# servo_power.net
KiCad netlist of a schematic drawn in EAGLE
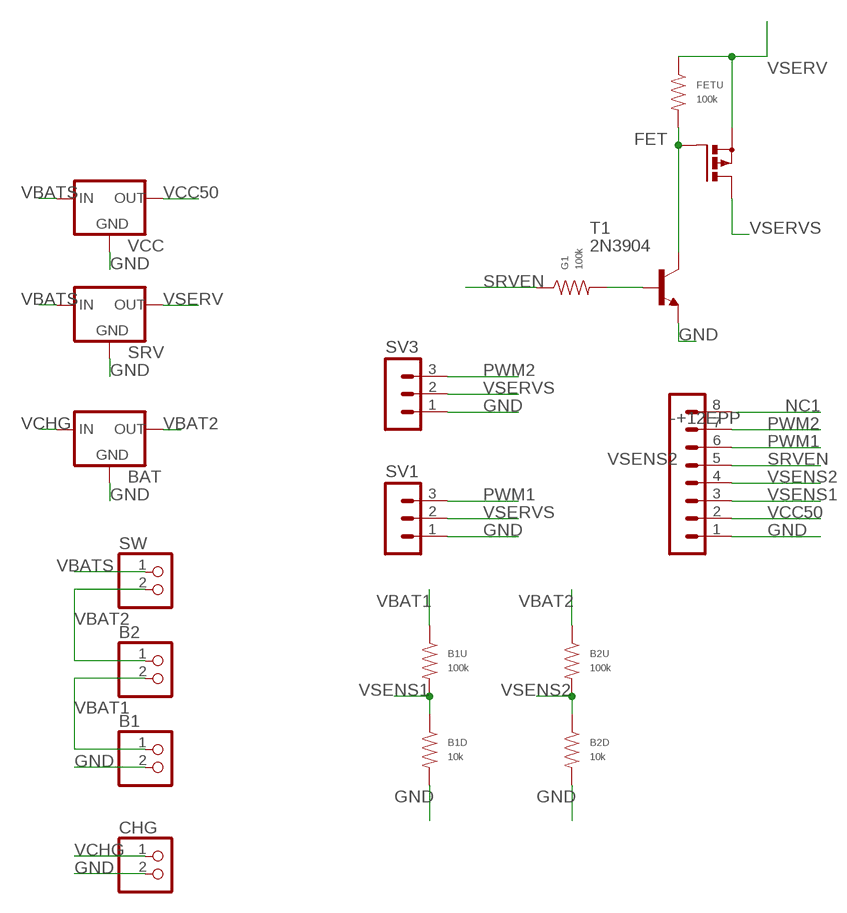
[diagram p0: schematic, sheet 1]

(export (version "E")
  (design (tool "Eeschema 10.0.6"))
  (components
    (comp (ref "-+12EPP")
      (value "MA08-1")
      (footprint "eagle-import:MA08-1")
      (libsource (lib "eagle-import") (part "MA08-1"))
    )
    (comp (ref "B1")
      (value "PINHD-1X2")
      (footprint "eagle-import:1X02")
      (libsource (lib "eagle-import") (part "PINHD-1X2"))
    )
    (comp (ref "B1D")
      (value "10k")
      (footprint "eagle-import:R1206")
      (libsource (lib "eagle-import") (part "RESISTOR_1206"))
    )
    (comp (ref "B1U")
      (value "100k")
      (footprint "eagle-import:R1206")
      (libsource (lib "eagle-import") (part "RESISTOR_1206"))
    )
    (comp (ref "B2")
      (value "PINHD-1X2")
      (footprint "eagle-import:1X02")
      (libsource (lib "eagle-import") (part "PINHD-1X2"))
    )
    (comp (ref "B2D")
      (value "10k")
      (footprint "eagle-import:R1206")
      (libsource (lib "eagle-import") (part "RESISTOR_1206"))
    )
    (comp (ref "B2U")
      (value "100k")
      (footprint "eagle-import:R1206")
      (libsource (lib "eagle-import") (part "RESISTOR_1206"))
    )
    (comp (ref "BAT")
      (value "78XXS")
      (footprint "eagle-import:78XXS")
      (libsource (lib "eagle-import") (part "78XXS"))
    )
    (comp (ref "CHG")
      (value "PINHD-1X2")
      (footprint "eagle-import:1X02")
      (libsource (lib "eagle-import") (part "PINHD-1X2"))
    )
    (comp (ref "FET")
      (value "PMOSFET_PTO220BV")
      (footprint "eagle-import:TO220BV")
      (libsource (lib "eagle-import") (part "PMOSFET_PTO220BV"))
    )
    (comp (ref "FETU")
      (value "100k")
      (footprint "eagle-import:R1206")
      (libsource (lib "eagle-import") (part "RESISTOR_1206"))
    )
    (comp (ref "G1")
      (value "100k")
      (footprint "eagle-import:R1206")
      (libsource (lib "eagle-import") (part "RESISTOR_1206"))
    )
    (comp (ref "SRV")
      (value "78XXS")
      (footprint "eagle-import:78XXS")
      (libsource (lib "eagle-import") (part "78XXS"))
    )
    (comp (ref "SV1")
      (value "MA03-1")
      (footprint "eagle-import:MA03-1")
      (libsource (lib "eagle-import") (part "MA03-1"))
    )
    (comp (ref "SV3")
      (value "MA03-1")
      (footprint "eagle-import:MA03-1")
      (libsource (lib "eagle-import") (part "MA03-1"))
    )
    (comp (ref "SW")
      (value "PINHD-1X2")
      (footprint "eagle-import:1X02")
      (libsource (lib "eagle-import") (part "PINHD-1X2"))
    )
    (comp (ref "T1")
      (value "2N3904")
      (footprint "eagle-import:TO92")
      (libsource (lib "eagle-import") (part "2N3904"))
    )
    (comp (ref "VCC")
      (value "78XXS")
      (footprint "eagle-import:78XXS")
      (libsource (lib "eagle-import") (part "78XXS"))
    )
  )
  (nets
    (net (code "1") (name "GND") (class "Default")
      (node (ref "-+12EPP") (pin "1") (pinfunction "1_1") (pintype "passive"))
      (node (ref "B1") (pin "2") (pinfunction "2_2") (pintype "passive"))
      (node (ref "B1D") (pin "P$2") (pinfunction "P$2_P$2") (pintype "passive"))
      (node (ref "B2D") (pin "P$2") (pinfunction "P$2_P$2") (pintype "passive"))
      (node (ref "BAT") (pin "GND") (pinfunction "GND_GND") (pintype "input"))
      (node (ref "CHG") (pin "2") (pinfunction "2_2") (pintype "passive"))
      (node (ref "SRV") (pin "GND") (pinfunction "GND_GND") (pintype "input"))
      (node (ref "SV1") (pin "1") (pinfunction "1_1") (pintype "passive"))
      (node (ref "SV3") (pin "1") (pinfunction "1_1") (pintype "passive"))
      (node (ref "T1") (pin "3") (pinfunction "E_3") (pintype "passive"))
      (node (ref "VCC") (pin "GND") (pinfunction "GND_GND") (pintype "input"))
    )
    (net (code "2") (name "NC1") (class "Default")
      (node (ref "-+12EPP") (pin "8") (pinfunction "8_8") (pintype "passive"))
    )
    (net (code "3") (name "Net-(T1-B)") (class "Default")
      (node (ref "G1") (pin "P$2") (pinfunction "P$2_P$2") (pintype "passive"))
      (node (ref "T1") (pin "2") (pinfunction "B_2") (pintype "passive"))
    )
    (net (code "4") (name "Net-(T1-C)") (class "Default")
      (node (ref "FET") (pin "G") (pinfunction "G_G") (pintype "passive"))
      (node (ref "FETU") (pin "P$2") (pinfunction "P$2_P$2") (pintype "passive"))
      (node (ref "T1") (pin "1") (pinfunction "C_1") (pintype "passive"))
    )
    (net (code "5") (name "PWM1") (class "Default")
      (node (ref "-+12EPP") (pin "6") (pinfunction "6_6") (pintype "passive"))
      (node (ref "SV1") (pin "3") (pinfunction "3_3") (pintype "passive"))
    )
    (net (code "6") (name "PWM2") (class "Default")
      (node (ref "-+12EPP") (pin "7") (pinfunction "7_7") (pintype "passive"))
      (node (ref "SV3") (pin "3") (pinfunction "3_3") (pintype "passive"))
    )
    (net (code "7") (name "SRVEN") (class "Default")
      (node (ref "-+12EPP") (pin "5") (pinfunction "5_5") (pintype "passive"))
      (node (ref "G1") (pin "P$1") (pinfunction "P$1_P$1") (pintype "passive"))
    )
    (net (code "8") (name "VBAT1") (class "Default")
      (node (ref "B1") (pin "1") (pinfunction "1_1") (pintype "passive"))
      (node (ref "B1U") (pin "P$1") (pinfunction "P$1_P$1") (pintype "passive"))
      (node (ref "B2") (pin "2") (pinfunction "2_2") (pintype "passive"))
    )
    (net (code "9") (name "VBAT2") (class "Default")
      (node (ref "B2") (pin "1") (pinfunction "1_1") (pintype "passive"))
      (node (ref "B2U") (pin "P$1") (pinfunction "P$1_P$1") (pintype "passive"))
      (node (ref "BAT") (pin "OUT") (pinfunction "OUT_OUT") (pintype "passive"))
      (node (ref "SW") (pin "2") (pinfunction "2_2") (pintype "passive"))
    )
    (net (code "10") (name "VBATS") (class "Default")
      (node (ref "SRV") (pin "IN") (pinfunction "IN_IN") (pintype "input"))
      (node (ref "SW") (pin "1") (pinfunction "1_1") (pintype "passive"))
      (node (ref "VCC") (pin "IN") (pinfunction "IN_IN") (pintype "input"))
    )
    (net (code "11") (name "VCC50") (class "Default")
      (node (ref "-+12EPP") (pin "2") (pinfunction "2_2") (pintype "passive"))
      (node (ref "VCC") (pin "OUT") (pinfunction "OUT_OUT") (pintype "passive"))
    )
    (net (code "12") (name "VCHG") (class "Default")
      (node (ref "BAT") (pin "IN") (pinfunction "IN_IN") (pintype "input"))
      (node (ref "CHG") (pin "1") (pinfunction "1_1") (pintype "passive"))
    )
    (net (code "13") (name "VSENS1") (class "Default")
      (node (ref "-+12EPP") (pin "3") (pinfunction "3_3") (pintype "passive"))
      (node (ref "B1D") (pin "P$1") (pinfunction "P$1_P$1") (pintype "passive"))
      (node (ref "B1U") (pin "P$2") (pinfunction "P$2_P$2") (pintype "passive"))
    )
    (net (code "14") (name "VSENS2") (class "Default")
      (node (ref "-+12EPP") (pin "4") (pinfunction "4_4") (pintype "passive"))
      (node (ref "B2D") (pin "P$1") (pinfunction "P$1_P$1") (pintype "passive"))
      (node (ref "B2U") (pin "P$2") (pinfunction "P$2_P$2") (pintype "passive"))
    )
    (net (code "15") (name "VSERV") (class "Default")
      (node (ref "FET") (pin "S") (pinfunction "S_S") (pintype "passive"))
      (node (ref "FETU") (pin "P$1") (pinfunction "P$1_P$1") (pintype "passive"))
      (node (ref "SRV") (pin "OUT") (pinfunction "OUT_OUT") (pintype "passive"))
    )
    (net (code "16") (name "VSERVS") (class "Default")
      (node (ref "FET") (pin "D") (pinfunction "D_D") (pintype "passive"))
      (node (ref "SV1") (pin "2") (pinfunction "2_2") (pintype "passive"))
      (node (ref "SV3") (pin "2") (pinfunction "2_2") (pintype "passive"))
    )
  )
)
